# CPbyTimmer555.net
KiCad netlist of a schematic drawn in EAGLE
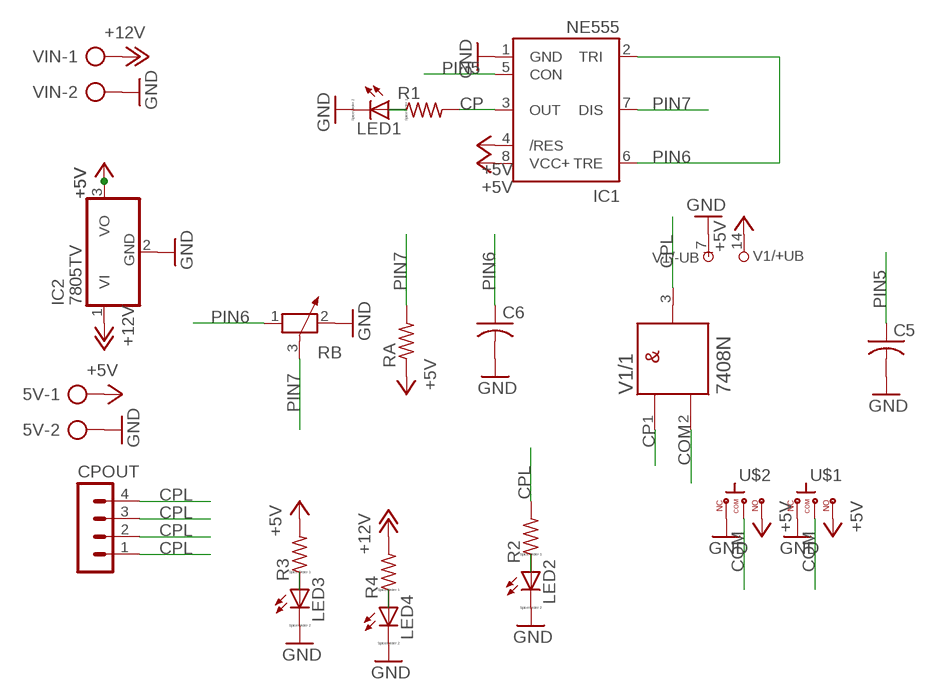
[diagram p0: schematic, sheet 1]

(export (version "E")
  (design (tool "Eeschema 10.0.6"))
  (components
    (comp (ref "5V")
      (value "AK500/2-H")
      (footprint "eagle-import:AK500_2-H")
      (libsource (lib "eagle-import") (part "AK500/2-H"))
    )
    (comp (ref "C5")
      (value "C-US025-025X050")
      (footprint "eagle-import:C025-025X050")
      (libsource (lib "eagle-import") (part "C-US025-025X050"))
    )
    (comp (ref "C6")
      (value "C-US025-025X050")
      (footprint "eagle-import:C025-025X050")
      (libsource (lib "eagle-import") (part "C-US025-025X050"))
    )
    (comp (ref "CPOUT")
      (value "MA04-1")
      (footprint "eagle-import:MA04-1")
      (libsource (lib "eagle-import") (part "MA04-1"))
    )
    (comp (ref "IC1")
      (value "NE555")
      (footprint "eagle-import:DIL-08")
      (fields (field (name "MF") "Arrow Electronics") (field (name "MPN") "NE555N"))
      (libsource (lib "eagle-import") (part "NE555"))
    )
    (comp (ref "IC2")
      (value "7805TV")
      (footprint "eagle-import:TO220V")
      (libsource (lib "eagle-import") (part "78TV05"))
    )
    (comp (ref "LED1")
      (value "LED_ELD260")
      (footprint "eagle-import:LED_LD260")
      (libsource (lib "eagle-import") (part "LED_ELD260"))
    )
    (comp (ref "LED2")
      (value "LED_ELD260")
      (footprint "eagle-import:LED_LD260")
      (libsource (lib "eagle-import") (part "LED_ELD260"))
    )
    (comp (ref "LED3")
      (value "LED_ELD260")
      (footprint "eagle-import:LED_LD260")
      (libsource (lib "eagle-import") (part "LED_ELD260"))
    )
    (comp (ref "LED4")
      (value "LED_ELD260")
      (footprint "eagle-import:LED_LD260")
      (libsource (lib "eagle-import") (part "LED_ELD260"))
    )
    (comp (ref "R1")
      (value "R-US_0204/5")
      (footprint "eagle-import:0204_5")
      (libsource (lib "eagle-import") (part "R-US_0204/5"))
    )
    (comp (ref "R2")
      (value "R-US_0204/5")
      (footprint "eagle-import:0204_5")
      (libsource (lib "eagle-import") (part "R-US_0204/5"))
    )
    (comp (ref "R3")
      (value "R-US_0204/5")
      (footprint "eagle-import:0204_5")
      (libsource (lib "eagle-import") (part "R-US_0204/5"))
    )
    (comp (ref "R4")
      (value "R-US_0204/5")
      (footprint "eagle-import:0204_5")
      (libsource (lib "eagle-import") (part "R-US_0204/5"))
    )
    (comp (ref "RA")
      (value "R-US_0204/5")
      (footprint "eagle-import:0204_5")
      (libsource (lib "eagle-import") (part "R-US_0204/5"))
    )
    (comp (ref "RB")
      (value "POTENTIOMETER_PT-10")
      (footprint "eagle-import:PT-10")
      (libsource (lib "eagle-import") (part "POTENTIOMETER_PT-10"))
    )
    (comp (ref "U$1")
      (value "-SWITCH")
      (footprint "eagle-import:CON3")
      (libsource (lib "eagle-import") (part "-SWITCH"))
    )
    (comp (ref "U$2")
      (value "-SWITCH")
      (footprint "eagle-import:CON3")
      (libsource (lib "eagle-import") (part "-SWITCH"))
    )
    (comp (ref "V1")
      (value "7408N")
      (footprint "eagle-import:DIL14")
      (libsource (lib "eagle-import") (part "7408N"))
    )
    (comp (ref "VIN")
      (value "AK500/2-H")
      (footprint "eagle-import:AK500_2-H")
      (libsource (lib "eagle-import") (part "AK500/2-H"))
    )
  )
  (nets
    (net (code "1") (name "+5V") (class "Default")
      (node (ref "5V") (pin "1") (pinfunction "KL_1") (pintype "passive"))
      (node (ref "IC1") (pin "4") (pinfunction "/RES_4") (pintype "input"))
      (node (ref "IC1") (pin "8") (pinfunction "VCC+_8") (pintype "power_in"))
      (node (ref "IC2") (pin "3") (pinfunction "VO_3") (pintype "passive"))
      (node (ref "R3") (pin "2") (pinfunction "2_2") (pintype "passive"))
      (node (ref "RA") (pin "1") (pinfunction "1_1") (pintype "passive"))
      (node (ref "U$1") (pin "P$3") (pinfunction "3_P$3") (pintype "passive"))
      (node (ref "U$2") (pin "P$3") (pinfunction "3_P$3") (pintype "passive"))
      (node (ref "V1") (pin "14") (pinfunction "+UB_14") (pintype "power_in"))
    )
    (net (code "2") (name "+12V") (class "Default")
      (node (ref "IC2") (pin "1") (pinfunction "VI_1") (pintype "input"))
      (node (ref "R4") (pin "2") (pinfunction "2_2") (pintype "passive"))
      (node (ref "VIN") (pin "1") (pinfunction "KL_1") (pintype "passive"))
    )
    (net (code "3") (name "/COM") (class "Default")
      (node (ref "U$1") (pin "P$2") (pinfunction "2_P$2") (pintype "passive"))
      (node (ref "U$2") (pin "P$2") (pinfunction "2_P$2") (pintype "passive"))
      (node (ref "V1") (pin "2") (pinfunction "B_2") (pintype "input"))
    )
    (net (code "4") (name "/CP") (class "Default")
      (node (ref "IC1") (pin "3") (pinfunction "OUT_3") (pintype "output"))
      (node (ref "R1") (pin "2") (pinfunction "2_2") (pintype "passive"))
      (node (ref "V1") (pin "1") (pinfunction "A_1") (pintype "input"))
    )
    (net (code "5") (name "/CPL") (class "Default")
      (node (ref "CPOUT") (pin "1") (pinfunction "1_1") (pintype "passive"))
      (node (ref "CPOUT") (pin "2") (pinfunction "2_2") (pintype "passive"))
      (node (ref "CPOUT") (pin "3") (pinfunction "3_3") (pintype "passive"))
      (node (ref "CPOUT") (pin "4") (pinfunction "4_4") (pintype "passive"))
      (node (ref "R2") (pin "2") (pinfunction "2_2") (pintype "passive"))
      (node (ref "V1") (pin "3") (pinfunction "Y_3") (pintype "output"))
    )
    (net (code "6") (name "/PIN5") (class "Default")
      (node (ref "C5") (pin "1") (pinfunction "1_1") (pintype "passive"))
      (node (ref "IC1") (pin "5") (pinfunction "CON_5") (pintype "input"))
    )
    (net (code "7") (name "/PIN6") (class "Default")
      (node (ref "C6") (pin "1") (pinfunction "1_1") (pintype "passive"))
      (node (ref "IC1") (pin "2") (pinfunction "TRI_2") (pintype "input"))
      (node (ref "IC1") (pin "6") (pinfunction "TRE_6") (pintype "input"))
      (node (ref "RB") (pin "1") (pinfunction "1_1") (pintype "passive"))
    )
    (net (code "8") (name "/PIN7") (class "Default")
      (node (ref "IC1") (pin "7") (pinfunction "DIS_7") (pintype "input"))
      (node (ref "RA") (pin "2") (pinfunction "2_2") (pintype "passive"))
      (node (ref "RB") (pin "3") (pinfunction "3_3") (pintype "passive"))
    )
    (net (code "9") (name "GND") (class "Default")
      (node (ref "5V") (pin "2") (pinfunction "KL_2") (pintype "passive"))
      (node (ref "C5") (pin "2") (pinfunction "2_2") (pintype "passive"))
      (node (ref "C6") (pin "2") (pinfunction "2_2") (pintype "passive"))
      (node (ref "IC1") (pin "1") (pinfunction "GND_1") (pintype "power_in"))
      (node (ref "IC2") (pin "2") (pinfunction "GND_2") (pintype "passive"))
      (node (ref "LED1") (pin "K") (pinfunction "C_K") (pintype "passive"))
      (node (ref "LED2") (pin "K") (pinfunction "C_K") (pintype "passive"))
      (node (ref "LED3") (pin "K") (pinfunction "C_K") (pintype "passive"))
      (node (ref "LED4") (pin "K") (pinfunction "C_K") (pintype "passive"))
      (node (ref "RB") (pin "2") (pinfunction "2_2") (pintype "passive"))
      (node (ref "U$1") (pin "P$1") (pinfunction "1_P$1") (pintype "passive"))
      (node (ref "U$2") (pin "P$1") (pinfunction "1_P$1") (pintype "passive"))
      (node (ref "V1") (pin "7") (pinfunction "-UB_7") (pintype "power_in"))
      (node (ref "VIN") (pin "2") (pinfunction "KL_2") (pintype "passive"))
    )
    (net (code "10") (name "Net-(LED1-PadA)") (class "Default")
      (node (ref "LED1") (pin "A") (pinfunction "A_A") (pintype "passive"))
      (node (ref "R1") (pin "1") (pinfunction "1_1") (pintype "passive"))
    )
    (net (code "11") (name "Net-(LED2-PadA)") (class "Default")
      (node (ref "LED2") (pin "A") (pinfunction "A_A") (pintype "passive"))
      (node (ref "R2") (pin "1") (pinfunction "1_1") (pintype "passive"))
    )
    (net (code "12") (name "Net-(LED3-PadA)") (class "Default")
      (node (ref "LED3") (pin "A") (pinfunction "A_A") (pintype "passive"))
      (node (ref "R3") (pin "1") (pinfunction "1_1") (pintype "passive"))
    )
    (net (code "13") (name "Net-(LED4-PadA)") (class "Default")
      (node (ref "LED4") (pin "A") (pinfunction "A_A") (pintype "passive"))
      (node (ref "R4") (pin "1") (pinfunction "1_1") (pintype "passive"))
    )
  )
)
